# X7A15T-Fabric.net
KiCad netlist of a schematic drawn in Altium Designer
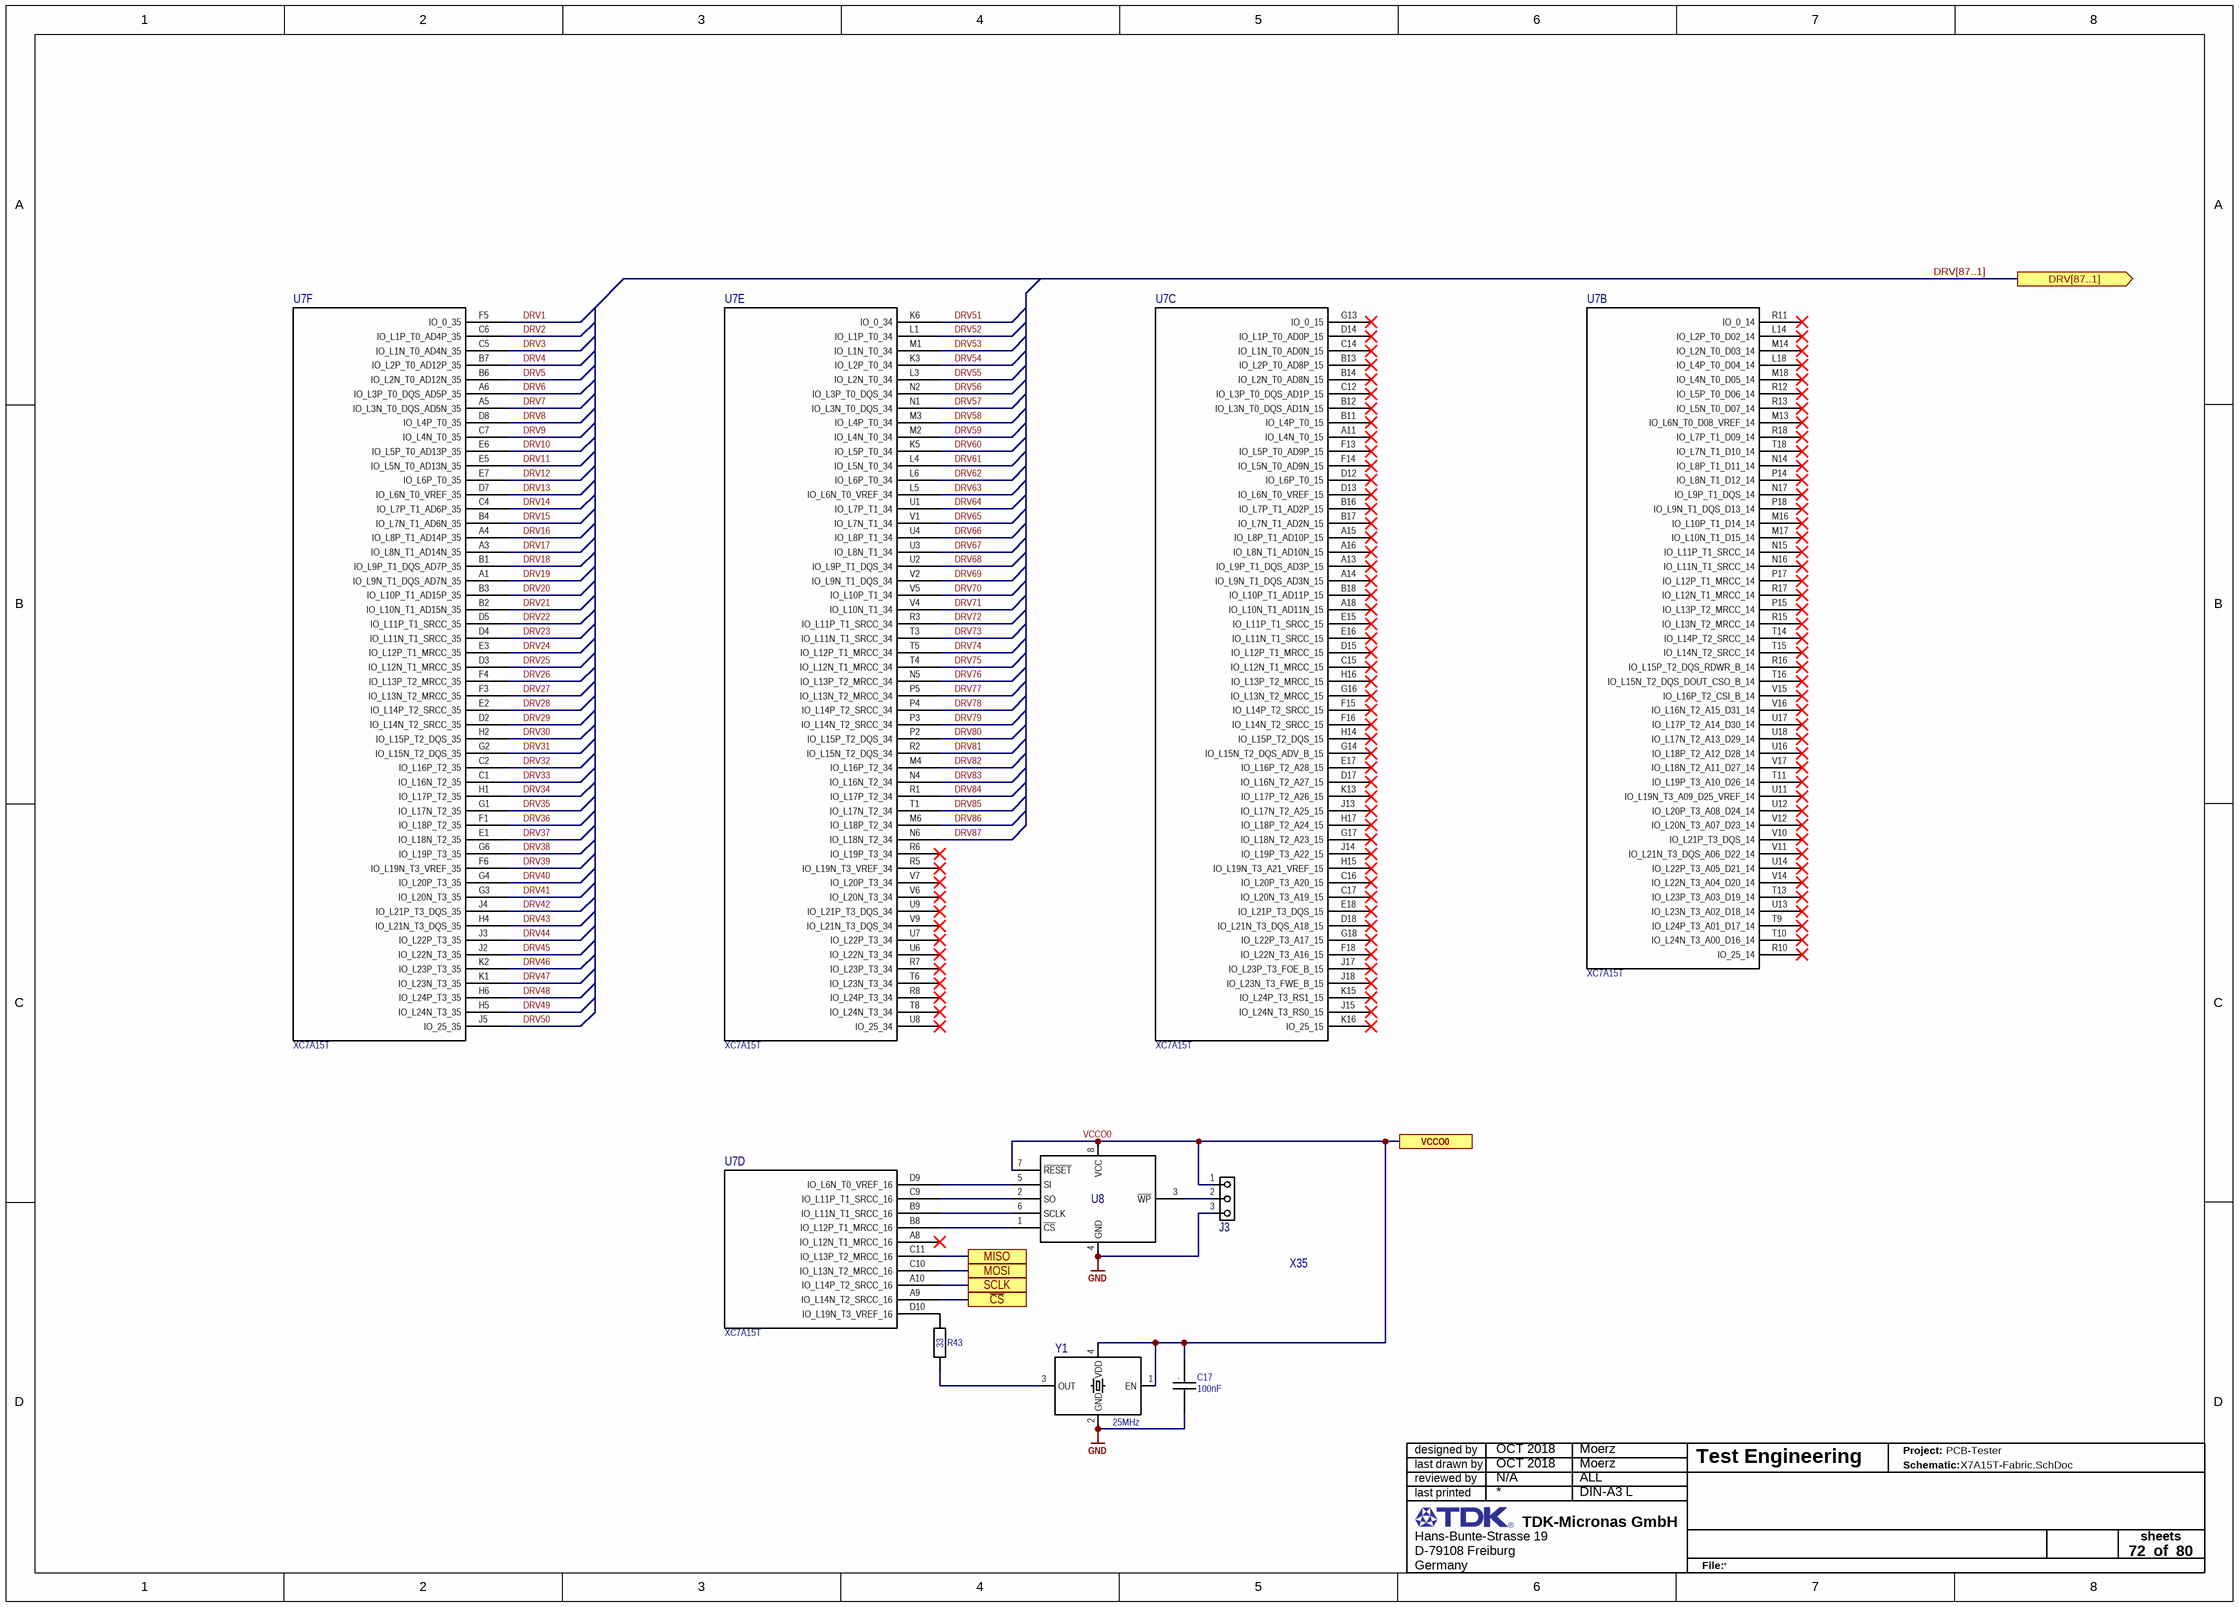
[diagram p0: X7A15T-Fabric.SchDoc]

(export (version "E")
  (design (tool "Eeschema 10.0.6"))
  (components
    (comp (ref "C17")
      (value "100nF")
      (footprint "C0402 Reflow")
      (description "CAP CER 0.1UF 16V X7R 0402")
      (fields
        (field (name "TOLERANCE") "±5%")
        (field (name "02. DISTRIBUTOR PART NUMBER") "399-7761-6-ND")
        (field (name "13. CREATED DATE/NAME") "AUG2018/Hören")
      )
      (libsource (lib "chickenfood") (part "C"))
    )
    (comp (ref "J3")
      (value "J")
      (footprint "Header 100mil 3x1")
      (description "CONN HEADER VERT 3POS 2.54MM")
      (fields
        (field (name "02. DISTRIBUTOR PART NUMBER") "HMTSW-103-07-G-S-240")
        (field (name "13. CREATED DATE/NAME") "AUG2018/Hören")
      )
      (libsource (lib "chickenfood") (part "Header 3Pins 100mil"))
    )
    (comp (ref "R43")
      (value "33")
      (footprint "R0402 Reflow")
      (description "RES SMD 33 OHM 1% 1/16W 0402")
      (fields
        (field (name "TOLERANCE") "±1%")
        (field (name "02. DISTRIBUTOR PART NUMBER") "311-33.0LRDKR-ND")
        (field (name "13. CREATED DATE/NAME") "AUG2018/Hören")
      )
      (libsource (lib "chickenfood") (part "R"))
    )
    (comp (ref "U7")
      (value "U")
      (footprint "XC7A15T-1CSG324C")
      (description "XC7A15T-1CSG324C")
      (fields (field (name "MFR") "XILINX") (field (name "NICNAME") "XC7A15T"))
      (libsource (lib "tom") (part "XC7A15T-CS324"))
    )
    (comp (ref "U8")
      (value "U")
      (footprint "SOIC8 (R-8)")
      (description "IC FLASH 32M SPI 80MHZ 8SOP")
      (fields (field (name "13. CREATED DATE/NAME") "AUG 2018 / Hören"))
      (libsource (lib "tom") (part "MX25R3235FM1IH0"))
    )
    (comp (ref "X35")
      (value "X")
      (description "CONN JUMPER SHORTING .100\" GOLD")
      (fields
        (field (name "02. DISTRIBUTOR PART NUMBER") "S9337-ND")
        (field (name "07. MANUFACTURER  PART NUMBER") "QPC02SXGN-RC")
        (field (name "13. CREATED DATE/NAME") "AUG2018/Hören")
      )
      (libsource (lib "chickenfood") (part "Jumper"))
    )
    (comp (ref "Y1")
      (value "Y")
      (footprint "4SMD")
      (description "XTAL OSC XO 25.0000MHZ CMOS SMD")
      (fields
        (field (name "02. DISTRIBUTOR PART NUMBER") "535-9568-1-ND")
        (field (name "07. MANUFACTURER  PART NUMBER") "ASE-25.000MHZ-LC-T")
        (field (name "FREQUENCY") "25MHz")
        (field (name "13. CREATED DATE/NAME") "AUG 2018 / Hören")
      )
      (libsource (lib "tom") (part "ASE-25.000MHZ-LC-T"))
    )
  )
  (nets
    (net (code "1") (name "/CS") (class "Default")
      (node (ref "U7") (pin "A9") (pinfunction "IO_L14N_T2_SRCC_16_A9") (pintype "passive"))
    )
    (net (code "2") (name "/DRV1") (class "Default")
      (node (ref "U7") (pin "F5") (pinfunction "IO_0_35_F5") (pintype "passive"))
    )
    (net (code "3") (name "/DRV2") (class "Default")
      (node (ref "U7") (pin "C6") (pinfunction "IO_L1P_T0_AD4P_35_C6") (pintype "passive"))
    )
    (net (code "4") (name "/DRV3") (class "Default")
      (node (ref "U7") (pin "C5") (pinfunction "IO_L1N_T0_AD4N_35_C5") (pintype "passive"))
    )
    (net (code "5") (name "/DRV4") (class "Default")
      (node (ref "U7") (pin "B7") (pinfunction "IO_L2P_T0_AD12P_35_B7") (pintype "passive"))
    )
    (net (code "6") (name "/DRV5") (class "Default")
      (node (ref "U7") (pin "B6") (pinfunction "IO_L2N_T0_AD12N_35_B6") (pintype "passive"))
    )
    (net (code "7") (name "/DRV6") (class "Default")
      (node (ref "U7") (pin "A6") (pinfunction "IO_L3P_T0_DQS_AD5P_35_A6") (pintype "passive"))
    )
    (net (code "8") (name "/DRV7") (class "Default")
      (node (ref "U7") (pin "A5") (pinfunction "IO_L3N_T0_DQS_AD5N_35_A5") (pintype "passive"))
    )
    (net (code "9") (name "/DRV8") (class "Default")
      (node (ref "U7") (pin "D8") (pinfunction "IO_L4P_T0_35_D8") (pintype "passive"))
    )
    (net (code "10") (name "/DRV9") (class "Default")
      (node (ref "U7") (pin "C7") (pinfunction "IO_L4N_T0_35_C7") (pintype "passive"))
    )
    (net (code "11") (name "/DRV10") (class "Default")
      (node (ref "U7") (pin "E6") (pinfunction "IO_L5P_T0_AD13P_35_E6") (pintype "passive"))
    )
    (net (code "12") (name "/DRV11") (class "Default")
      (node (ref "U7") (pin "E5") (pinfunction "IO_L5N_T0_AD13N_35_E5") (pintype "passive"))
    )
    (net (code "13") (name "/DRV12") (class "Default")
      (node (ref "U7") (pin "E7") (pinfunction "IO_L6P_T0_35_E7") (pintype "passive"))
    )
    (net (code "14") (name "/DRV13") (class "Default")
      (node (ref "U7") (pin "D7") (pinfunction "IO_L6N_T0_VREF_35_D7") (pintype "passive"))
    )
    (net (code "15") (name "/DRV14") (class "Default")
      (node (ref "U7") (pin "C4") (pinfunction "IO_L7P_T1_AD6P_35_C4") (pintype "passive"))
    )
    (net (code "16") (name "/DRV15") (class "Default")
      (node (ref "U7") (pin "B4") (pinfunction "IO_L7N_T1_AD6N_35_B4") (pintype "passive"))
    )
    (net (code "17") (name "/DRV16") (class "Default")
      (node (ref "U7") (pin "A4") (pinfunction "IO_L8P_T1_AD14P_35_A4") (pintype "passive"))
    )
    (net (code "18") (name "/DRV17") (class "Default")
      (node (ref "U7") (pin "A3") (pinfunction "IO_L8N_T1_AD14N_35_A3") (pintype "passive"))
    )
    (net (code "19") (name "/DRV18") (class "Default")
      (node (ref "U7") (pin "B1") (pinfunction "IO_L9P_T1_DQS_AD7P_35_B1") (pintype "passive"))
    )
    (net (code "20") (name "/DRV19") (class "Default")
      (node (ref "U7") (pin "A1") (pinfunction "IO_L9N_T1_DQS_AD7N_35_A1") (pintype "passive"))
    )
    (net (code "21") (name "/DRV20") (class "Default")
      (node (ref "U7") (pin "B3") (pinfunction "IO_L10P_T1_AD15P_35_B3") (pintype "passive"))
    )
    (net (code "22") (name "/DRV21") (class "Default")
      (node (ref "U7") (pin "B2") (pinfunction "IO_L10N_T1_AD15N_35_B2") (pintype "passive"))
    )
    (net (code "23") (name "/DRV22") (class "Default")
      (node (ref "U7") (pin "D5") (pinfunction "IO_L11P_T1_SRCC_35_D5") (pintype "passive"))
    )
    (net (code "24") (name "/DRV23") (class "Default")
      (node (ref "U7") (pin "D4") (pinfunction "IO_L11N_T1_SRCC_35_D4") (pintype "passive"))
    )
    (net (code "25") (name "/DRV24") (class "Default")
      (node (ref "U7") (pin "E3") (pinfunction "IO_L12P_T1_MRCC_35_E3") (pintype "passive"))
    )
    (net (code "26") (name "/DRV25") (class "Default")
      (node (ref "U7") (pin "D3") (pinfunction "IO_L12N_T1_MRCC_35_D3") (pintype "passive"))
    )
    (net (code "27") (name "/DRV26") (class "Default")
      (node (ref "U7") (pin "F4") (pinfunction "IO_L13P_T2_MRCC_35_F4") (pintype "passive"))
    )
    (net (code "28") (name "/DRV27") (class "Default")
      (node (ref "U7") (pin "F3") (pinfunction "IO_L13N_T2_MRCC_35_F3") (pintype "passive"))
    )
    (net (code "29") (name "/DRV28") (class "Default")
      (node (ref "U7") (pin "E2") (pinfunction "IO_L14P_T2_SRCC_35_E2") (pintype "passive"))
    )
    (net (code "30") (name "/DRV29") (class "Default")
      (node (ref "U7") (pin "D2") (pinfunction "IO_L14N_T2_SRCC_35_D2") (pintype "passive"))
    )
    (net (code "31") (name "/DRV30") (class "Default")
      (node (ref "U7") (pin "H2") (pinfunction "IO_L15P_T2_DQS_35_H2") (pintype "passive"))
    )
    (net (code "32") (name "/DRV31") (class "Default")
      (node (ref "U7") (pin "G2") (pinfunction "IO_L15N_T2_DQS_35_G2") (pintype "passive"))
    )
    (net (code "33") (name "/DRV32") (class "Default")
      (node (ref "U7") (pin "C2") (pinfunction "IO_L16P_T2_35_C2") (pintype "passive"))
    )
    (net (code "34") (name "/DRV33") (class "Default")
      (node (ref "U7") (pin "C1") (pinfunction "IO_L16N_T2_35_C1") (pintype "passive"))
    )
    (net (code "35") (name "/DRV34") (class "Default")
      (node (ref "U7") (pin "H1") (pinfunction "IO_L17P_T2_35_H1") (pintype "passive"))
    )
    (net (code "36") (name "/DRV35") (class "Default")
      (node (ref "U7") (pin "G1") (pinfunction "IO_L17N_T2_35_G1") (pintype "passive"))
    )
    (net (code "37") (name "/DRV36") (class "Default")
      (node (ref "U7") (pin "F1") (pinfunction "IO_L18P_T2_35_F1") (pintype "passive"))
    )
    (net (code "38") (name "/DRV37") (class "Default")
      (node (ref "U7") (pin "E1") (pinfunction "IO_L18N_T2_35_E1") (pintype "passive"))
    )
    (net (code "39") (name "/DRV38") (class "Default")
      (node (ref "U7") (pin "G6") (pinfunction "IO_L19P_T3_35_G6") (pintype "passive"))
    )
    (net (code "40") (name "/DRV39") (class "Default")
      (node (ref "U7") (pin "F6") (pinfunction "IO_L19N_T3_VREF_35_F6") (pintype "passive"))
    )
    (net (code "41") (name "/DRV40") (class "Default")
      (node (ref "U7") (pin "G4") (pinfunction "IO_L20P_T3_35_G4") (pintype "passive"))
    )
    (net (code "42") (name "/DRV41") (class "Default")
      (node (ref "U7") (pin "G3") (pinfunction "IO_L20N_T3_35_G3") (pintype "passive"))
    )
    (net (code "43") (name "/DRV42") (class "Default")
      (node (ref "U7") (pin "J4") (pinfunction "IO_L21P_T3_DQS_35_J4") (pintype "passive"))
    )
    (net (code "44") (name "/DRV43") (class "Default")
      (node (ref "U7") (pin "H4") (pinfunction "IO_L21N_T3_DQS_35_H4") (pintype "passive"))
    )
    (net (code "45") (name "/DRV44") (class "Default")
      (node (ref "U7") (pin "J3") (pinfunction "IO_L22P_T3_35_J3") (pintype "passive"))
    )
    (net (code "46") (name "/DRV45") (class "Default")
      (node (ref "U7") (pin "J2") (pinfunction "IO_L22N_T3_35_J2") (pintype "passive"))
    )
    (net (code "47") (name "/DRV46") (class "Default")
      (node (ref "U7") (pin "K2") (pinfunction "IO_L23P_T3_35_K2") (pintype "passive"))
    )
    (net (code "48") (name "/DRV47") (class "Default")
      (node (ref "U7") (pin "K1") (pinfunction "IO_L23N_T3_35_K1") (pintype "passive"))
    )
    (net (code "49") (name "/DRV48") (class "Default")
      (node (ref "U7") (pin "H6") (pinfunction "IO_L24P_T3_35_H6") (pintype "passive"))
    )
    (net (code "50") (name "/DRV49") (class "Default")
      (node (ref "U7") (pin "H5") (pinfunction "IO_L24N_T3_35_H5") (pintype "passive"))
    )
    (net (code "51") (name "/DRV50") (class "Default")
      (node (ref "U7") (pin "J5") (pinfunction "IO_25_35_J5") (pintype "passive"))
    )
    (net (code "52") (name "/DRV51") (class "Default")
      (node (ref "U7") (pin "K6") (pinfunction "IO_0_34_K6") (pintype "passive"))
    )
    (net (code "53") (name "/DRV52") (class "Default")
      (node (ref "U7") (pin "L1") (pinfunction "IO_L1P_T0_34_L1") (pintype "passive"))
    )
    (net (code "54") (name "/DRV53") (class "Default")
      (node (ref "U7") (pin "M1") (pinfunction "IO_L1N_T0_34_M1") (pintype "passive"))
    )
    (net (code "55") (name "/DRV54") (class "Default")
      (node (ref "U7") (pin "K3") (pinfunction "IO_L2P_T0_34_K3") (pintype "passive"))
    )
    (net (code "56") (name "/DRV55") (class "Default")
      (node (ref "U7") (pin "L3") (pinfunction "IO_L2N_T0_34_L3") (pintype "passive"))
    )
    (net (code "57") (name "/DRV56") (class "Default")
      (node (ref "U7") (pin "N2") (pinfunction "IO_L3P_T0_DQS_34_N2") (pintype "passive"))
    )
    (net (code "58") (name "/DRV57") (class "Default")
      (node (ref "U7") (pin "N1") (pinfunction "IO_L3N_T0_DQS_34_N1") (pintype "passive"))
    )
    (net (code "59") (name "/DRV58") (class "Default")
      (node (ref "U7") (pin "M3") (pinfunction "IO_L4P_T0_34_M3") (pintype "passive"))
    )
    (net (code "60") (name "/DRV59") (class "Default")
      (node (ref "U7") (pin "M2") (pinfunction "IO_L4N_T0_34_M2") (pintype "passive"))
    )
    (net (code "61") (name "/DRV60") (class "Default")
      (node (ref "U7") (pin "K5") (pinfunction "IO_L5P_T0_34_K5") (pintype "passive"))
    )
    (net (code "62") (name "/DRV61") (class "Default")
      (node (ref "U7") (pin "L4") (pinfunction "IO_L5N_T0_34_L4") (pintype "passive"))
    )
    (net (code "63") (name "/DRV62") (class "Default")
      (node (ref "U7") (pin "L6") (pinfunction "IO_L6P_T0_34_L6") (pintype "passive"))
    )
    (net (code "64") (name "/DRV63") (class "Default")
      (node (ref "U7") (pin "L5") (pinfunction "IO_L6N_T0_VREF_34_L5") (pintype "passive"))
    )
    (net (code "65") (name "/DRV64") (class "Default")
      (node (ref "U7") (pin "U1") (pinfunction "IO_L7P_T1_34_U1") (pintype "passive"))
    )
    (net (code "66") (name "/DRV65") (class "Default")
      (node (ref "U7") (pin "V1") (pinfunction "IO_L7N_T1_34_V1") (pintype "passive"))
    )
    (net (code "67") (name "/DRV66") (class "Default")
      (node (ref "U7") (pin "U4") (pinfunction "IO_L8P_T1_34_U4") (pintype "passive"))
    )
    (net (code "68") (name "/DRV67") (class "Default")
      (node (ref "U7") (pin "U3") (pinfunction "IO_L8N_T1_34_U3") (pintype "passive"))
    )
    (net (code "69") (name "/DRV68") (class "Default")
      (node (ref "U7") (pin "U2") (pinfunction "IO_L9P_T1_DQS_34_U2") (pintype "passive"))
    )
    (net (code "70") (name "/DRV69") (class "Default")
      (node (ref "U7") (pin "V2") (pinfunction "IO_L9N_T1_DQS_34_V2") (pintype "passive"))
    )
    (net (code "71") (name "/DRV70") (class "Default")
      (node (ref "U7") (pin "V5") (pinfunction "IO_L10P_T1_34_V5") (pintype "passive"))
    )
    (net (code "72") (name "/DRV71") (class "Default")
      (node (ref "U7") (pin "V4") (pinfunction "IO_L10N_T1_34_V4") (pintype "passive"))
    )
    (net (code "73") (name "/DRV72") (class "Default")
      (node (ref "U7") (pin "R3") (pinfunction "IO_L11P_T1_SRCC_34_R3") (pintype "passive"))
    )
    (net (code "74") (name "/DRV73") (class "Default")
      (node (ref "U7") (pin "T3") (pinfunction "IO_L11N_T1_SRCC_34_T3") (pintype "passive"))
    )
    (net (code "75") (name "/DRV74") (class "Default")
      (node (ref "U7") (pin "T5") (pinfunction "IO_L12P_T1_MRCC_34_T5") (pintype "passive"))
    )
    (net (code "76") (name "/DRV75") (class "Default")
      (node (ref "U7") (pin "T4") (pinfunction "IO_L12N_T1_MRCC_34_T4") (pintype "passive"))
    )
    (net (code "77") (name "/DRV76") (class "Default")
      (node (ref "U7") (pin "N5") (pinfunction "IO_L13P_T2_MRCC_34_N5") (pintype "passive"))
    )
    (net (code "78") (name "/DRV77") (class "Default")
      (node (ref "U7") (pin "P5") (pinfunction "IO_L13N_T2_MRCC_34_P5") (pintype "passive"))
    )
    (net (code "79") (name "/DRV78") (class "Default")
      (node (ref "U7") (pin "P4") (pinfunction "IO_L14P_T2_SRCC_34_P4") (pintype "passive"))
    )
    (net (code "80") (name "/DRV79") (class "Default")
      (node (ref "U7") (pin "P3") (pinfunction "IO_L14N_T2_SRCC_34_P3") (pintype "passive"))
    )
    (net (code "81") (name "/DRV80") (class "Default")
      (node (ref "U7") (pin "P2") (pinfunction "IO_L15P_T2_DQS_34_P2") (pintype "passive"))
    )
    (net (code "82") (name "/DRV81") (class "Default")
      (node (ref "U7") (pin "R2") (pinfunction "IO_L15N_T2_DQS_34_R2") (pintype "passive"))
    )
    (net (code "83") (name "/DRV82") (class "Default")
      (node (ref "U7") (pin "M4") (pinfunction "IO_L16P_T2_34_M4") (pintype "passive"))
    )
    (net (code "84") (name "/DRV83") (class "Default")
      (node (ref "U7") (pin "N4") (pinfunction "IO_L16N_T2_34_N4") (pintype "passive"))
    )
    (net (code "85") (name "/DRV84") (class "Default")
      (node (ref "U7") (pin "R1") (pinfunction "IO_L17P_T2_34_R1") (pintype "passive"))
    )
    (net (code "86") (name "/DRV85") (class "Default")
      (node (ref "U7") (pin "T1") (pinfunction "IO_L17N_T2_34_T1") (pintype "passive"))
    )
    (net (code "87") (name "/DRV86") (class "Default")
      (node (ref "U7") (pin "M6") (pinfunction "IO_L18P_T2_34_M6") (pintype "passive"))
    )
    (net (code "88") (name "/DRV87") (class "Default")
      (node (ref "U7") (pin "N6") (pinfunction "IO_L18N_T2_34_N6") (pintype "passive"))
    )
    (net (code "90") (name "/MISO") (class "Default")
      (node (ref "U7") (pin "C11") (pinfunction "IO_L13P_T2_MRCC_16_C11") (pintype "passive"))
    )
    (net (code "91") (name "/MOSI") (class "Default")
      (node (ref "U7") (pin "C10") (pinfunction "IO_L13N_T2_MRCC_16_C10") (pintype "passive"))
    )
    (net (code "92") (name "/SCLK") (class "Default")
      (node (ref "U7") (pin "A10") (pinfunction "IO_L14P_T2_SRCC_16_A10") (pintype "passive"))
    )
    (net (code "93") (name "/VCCO0") (class "Default")
      (node (ref "C17") (pin "1") (pinfunction "1_1") (pintype "passive"))
      (node (ref "J3") (pin "1") (pinfunction "1_1") (pintype "passive"))
      (node (ref "U8") (pin "7") (pinfunction "RESET_7") (pintype "passive"))
      (node (ref "U8") (pin "8") (pinfunction "VCC_8") (pintype "passive"))
      (node (ref "Y1") (pin "1") (pinfunction "EN_1") (pintype "passive"))
      (node (ref "Y1") (pin "4") (pinfunction "VDD_4") (pintype "passive"))
    )
    (net (code "94") (name "GND") (class "Default")
      (node (ref "C17") (pin "2") (pinfunction "2_2") (pintype "passive"))
      (node (ref "J3") (pin "3") (pinfunction "3_3") (pintype "passive"))
      (node (ref "U8") (pin "4") (pinfunction "GND_4") (pintype "passive"))
      (node (ref "Y1") (pin "2") (pinfunction "GND_2") (pintype "passive"))
    )
    (net (code "95") (name "Net-(U7D-IO_L6N_T0_VREF_16)") (class "Default")
      (node (ref "U7") (pin "D9") (pinfunction "IO_L6N_T0_VREF_16_D9") (pintype "passive"))
      (node (ref "U8") (pin "5") (pinfunction "SI_5") (pintype "passive"))
    )
    (net (code "96") (name "Net-(U7D-IO_L11N_T1_SRCC_16)") (class "Default")
      (node (ref "U7") (pin "B9") (pinfunction "IO_L11N_T1_SRCC_16_B9") (pintype "passive"))
      (node (ref "U8") (pin "6") (pinfunction "SCLK_6") (pintype "passive"))
    )
    (net (code "97") (name "Net-(U7D-IO_L11P_T1_SRCC_16)") (class "Default")
      (node (ref "U7") (pin "C9") (pinfunction "IO_L11P_T1_SRCC_16_C9") (pintype "passive"))
      (node (ref "U8") (pin "2") (pinfunction "SO_2") (pintype "passive"))
    )
    (net (code "98") (name "Net-(U7D-IO_L12P_T1_MRCC_16)") (class "Default")
      (node (ref "U7") (pin "B8") (pinfunction "IO_L12P_T1_MRCC_16_B8") (pintype "passive"))
      (node (ref "U8") (pin "1") (pinfunction "CS_1") (pintype "passive"))
    )
    (net (code "99") (name "Net-(U7D-IO_L19N_T3_VREF_16)") (class "Default")
      (node (ref "R43") (pin "2") (pinfunction "2_2") (pintype "passive"))
      (node (ref "U7") (pin "D10") (pinfunction "IO_L19N_T3_VREF_16_D10") (pintype "passive"))
    )
    (net (code "100") (name "Net-(U8-WP)") (class "Default")
      (node (ref "J3") (pin "2") (pinfunction "2_2") (pintype "passive"))
      (node (ref "U8") (pin "3") (pinfunction "WP_3") (pintype "passive"))
    )
    (net (code "101") (name "Net-(Y1-OUT)") (class "Default")
      (node (ref "R43") (pin "1") (pinfunction "1_1") (pintype "passive"))
      (node (ref "Y1") (pin "3") (pinfunction "OUT_3") (pintype "passive"))
    )
    (net (code "102") (name "unconnected-(U7B-IO_0_14-PadR11)") (class "Default")
      (node (ref "U7") (pin "R11") (pinfunction "IO_0_14_R11") (pintype "passive+no_connect"))
    )
    (net (code "103") (name "unconnected-(U7B-IO_25_14-PadR10)") (class "Default")
      (node (ref "U7") (pin "R10") (pinfunction "IO_25_14_R10") (pintype "passive+no_connect"))
    )
    (net (code "104") (name "unconnected-(U7B-IO_L2N_T0_D03_14-PadM14)") (class "Default")
      (node (ref "U7") (pin "M14") (pinfunction "IO_L2N_T0_D03_14_M14") (pintype "passive+no_connect"))
    )
    (net (code "105") (name "unconnected-(U7B-IO_L2P_T0_D02_14-PadL14)") (class "Default")
      (node (ref "U7") (pin "L14") (pinfunction "IO_L2P_T0_D02_14_L14") (pintype "passive+no_connect"))
    )
    (net (code "106") (name "unconnected-(U7B-IO_L4N_T0_D05_14-PadM18)") (class "Default")
      (node (ref "U7") (pin "M18") (pinfunction "IO_L4N_T0_D05_14_M18") (pintype "passive+no_connect"))
    )
    (net (code "107") (name "unconnected-(U7B-IO_L4P_T0_D04_14-PadL18)") (class "Default")
      (node (ref "U7") (pin "L18") (pinfunction "IO_L4P_T0_D04_14_L18") (pintype "passive+no_connect"))
    )
    (net (code "108") (name "unconnected-(U7B-IO_L5N_T0_D07_14-PadR13)") (class "Default")
      (node (ref "U7") (pin "R13") (pinfunction "IO_L5N_T0_D07_14_R13") (pintype "passive+no_connect"))
    )
    (net (code "109") (name "unconnected-(U7B-IO_L5P_T0_D06_14-PadR12)") (class "Default")
      (node (ref "U7") (pin "R12") (pinfunction "IO_L5P_T0_D06_14_R12") (pintype "passive+no_connect"))
    )
    (net (code "110") (name "unconnected-(U7B-IO_L6N_T0_D08_VREF_14-PadM13)") (class "Default")
      (node (ref "U7") (pin "M13") (pinfunction "IO_L6N_T0_D08_VREF_14_M13") (pintype "passive+no_connect"))
    )
    (net (code "111") (name "unconnected-(U7B-IO_L7N_T1_D10_14-PadT18)") (class "Default")
      (node (ref "U7") (pin "T18") (pinfunction "IO_L7N_T1_D10_14_T18") (pintype "passive+no_connect"))
    )
    (net (code "112") (name "unconnected-(U7B-IO_L7P_T1_D09_14-PadR18)") (class "Default")
      (node (ref "U7") (pin "R18") (pinfunction "IO_L7P_T1_D09_14_R18") (pintype "passive+no_connect"))
    )
    (net (code "113") (name "unconnected-(U7B-IO_L8N_T1_D12_14-PadP14)") (class "Default")
      (node (ref "U7") (pin "P14") (pinfunction "IO_L8N_T1_D12_14_P14") (pintype "passive+no_connect"))
    )
    (net (code "114") (name "unconnected-(U7B-IO_L8P_T1_D11_14-PadN14)") (class "Default")
      (node (ref "U7") (pin "N14") (pinfunction "IO_L8P_T1_D11_14_N14") (pintype "passive+no_connect"))
    )
    (net (code "115") (name "unconnected-(U7B-IO_L9N_T1_DQS_D13_14-PadP18)") (class "Default")
      (node (ref "U7") (pin "P18") (pinfunction "IO_L9N_T1_DQS_D13_14_P18") (pintype "passive+no_connect"))
    )
    (net (code "116") (name "unconnected-(U7B-IO_L9P_T1_DQS_14-PadN17)") (class "Default")
      (node (ref "U7") (pin "N17") (pinfunction "IO_L9P_T1_DQS_14_N17") (pintype "passive+no_connect"))
    )
    (net (code "117") (name "unconnected-(U7B-IO_L10N_T1_D15_14-PadM17)") (class "Default")
      (node (ref "U7") (pin "M17") (pinfunction "IO_L10N_T1_D15_14_M17") (pintype "passive+no_connect"))
    )
    (net (code "118") (name "unconnected-(U7B-IO_L10P_T1_D14_14-PadM16)") (class "Default")
      (node (ref "U7") (pin "M16") (pinfunction "IO_L10P_T1_D14_14_M16") (pintype "passive+no_connect"))
    )
    (net (code "119") (name "unconnected-(U7B-IO_L11N_T1_SRCC_14-PadN16)") (class "Default")
      (node (ref "U7") (pin "N16") (pinfunction "IO_L11N_T1_SRCC_14_N16") (pintype "passive+no_connect"))
    )
    (net (code "120") (name "unconnected-(U7B-IO_L11P_T1_SRCC_14-PadN15)") (class "Default")
      (node (ref "U7") (pin "N15") (pinfunction "IO_L11P_T1_SRCC_14_N15") (pintype "passive+no_connect"))
    )
    (net (code "121") (name "unconnected-(U7B-IO_L12N_T1_MRCC_14-PadR17)") (class "Default")
      (node (ref "U7") (pin "R17") (pinfunction "IO_L12N_T1_MRCC_14_R17") (pintype "passive+no_connect"))
    )
    (net (code "122") (name "unconnected-(U7B-IO_L12P_T1_MRCC_14-PadP17)") (class "Default")
      (node (ref "U7") (pin "P17") (pinfunction "IO_L12P_T1_MRCC_14_P17") (pintype "passive+no_connect"))
    )
    (net (code "123") (name "unconnected-(U7B-IO_L13N_T2_MRCC_14-PadR15)") (class "Default")
      (node (ref "U7") (pin "R15") (pinfunction "IO_L13N_T2_MRCC_14_R15") (pintype "passive+no_connect"))
    )
    (net (code "124") (name "unconnected-(U7B-IO_L13P_T2_MRCC_14-PadP15)") (class "Default")
      (node (ref "U7") (pin "P15") (pinfunction "IO_L13P_T2_MRCC_14_P15") (pintype "passive+no_connect"))
    )
    (net (code "125") (name "unconnected-(U7B-IO_L14N_T2_SRCC_14-PadT15)") (class "Default")
      (node (ref "U7") (pin "T15") (pinfunction "IO_L14N_T2_SRCC_14_T15") (pintype "passive+no_connect"))
    )
    (net (code "126") (name "unconnected-(U7B-IO_L14P_T2_SRCC_14-PadT14)") (class "Default")
      (node (ref "U7") (pin "T14") (pinfunction "IO_L14P_T2_SRCC_14_T14") (pintype "passive+no_connect"))
    )
    (net (code "127") (name "unconnected-(U7B-IO_L15N_T2_DQS_DOUT_CSO_B_14-PadT16)") (class "Default")
      (node (ref "U7") (pin "T16") (pinfunction "IO_L15N_T2_DQS_DOUT_CSO_B_14_T16") (pintype "passive+no_connect"))
    )
    (net (code "128") (name "unconnected-(U7B-IO_L15P_T2_DQS_RDWR_B_14-PadR16)") (class "Default")
      (node (ref "U7") (pin "R16") (pinfunction "IO_L15P_T2_DQS_RDWR_B_14_R16") (pintype "passive+no_connect"))
    )
    (net (code "129") (name "unconnected-(U7B-IO_L16N_T2_A15_D31_14-PadV16)") (class "Default")
      (node (ref "U7") (pin "V16") (pinfunction "IO_L16N_T2_A15_D31_14_V16") (pintype "passive+no_connect"))
    )
    (net (code "130") (name "unconnected-(U7B-IO_L16P_T2_CSI_B_14-PadV15)") (class "Default")
      (node (ref "U7") (pin "V15") (pinfunction "IO_L16P_T2_CSI_B_14_V15") (pintype "passive+no_connect"))
    )
    (net (code "131") (name "unconnected-(U7B-IO_L17N_T2_A13_D29_14-PadU18)") (class "Default")
      (node (ref "U7") (pin "U18") (pinfunction "IO_L17N_T2_A13_D29_14_U18") (pintype "passive+no_connect"))
    )
    (net (code "132") (name "unconnected-(U7B-IO_L17P_T2_A14_D30_14-PadU17)") (class "Default")
      (node (ref "U7") (pin "U17") (pinfunction "IO_L17P_T2_A14_D30_14_U17") (pintype "passive+no_connect"))
    )
    (net (code "133") (name "unconnected-(U7B-IO_L18N_T2_A11_D27_14-PadV17)") (class "Default")
      (node (ref "U7") (pin "V17") (pinfunction "IO_L18N_T2_A11_D27_14_V17") (pintype "passive+no_connect"))
    )
    (net (code "134") (name "unconnected-(U7B-IO_L18P_T2_A12_D28_14-PadU16)") (class "Default")
      (node (ref "U7") (pin "U16") (pinfunction "IO_L18P_T2_A12_D28_14_U16") (pintype "passive+no_connect"))
    )
    (net (code "135") (name "unconnected-(U7B-IO_L19N_T3_A09_D25_VREF_14-PadU11)") (class "Default")
      (node (ref "U7") (pin "U11") (pinfunction "IO_L19N_T3_A09_D25_VREF_14_U11") (pintype "passive+no_connect"))
    )
    (net (code "136") (name "unconnected-(U7B-IO_L19P_T3_A10_D26_14-PadT11)") (class "Default")
      (node (ref "U7") (pin "T11") (pinfunction "IO_L19P_T3_A10_D26_14_T11") (pintype "passive+no_connect"))
    )
    (net (code "137") (name "unconnected-(U7B-IO_L20N_T3_A07_D23_14-PadV12)") (class "Default")
      (node (ref "U7") (pin "V12") (pinfunction "IO_L20N_T3_A07_D23_14_V12") (pintype "passive+no_connect"))
    )
    (net (code "138") (name "unconnected-(U7B-IO_L20P_T3_A08_D24_14-PadU12)") (class "Default")
      (node (ref "U7") (pin "U12") (pinfunction "IO_L20P_T3_A08_D24_14_U12") (pintype "passive+no_connect"))
    )
    (net (code "139") (name "unconnected-(U7B-IO_L21N_T3_DQS_A06_D22_14-PadV11)") (class "Default")
      (node (ref "U7") (pin "V11") (pinfunction "IO_L21N_T3_DQS_A06_D22_14_V11") (pintype "passive+no_connect"))
    )
    (net (code "140") (name "unconnected-(U7B-IO_L21P_T3_DQS_14-PadV10)") (class "Default")
      (node (ref "U7") (pin "V10") (pinfunction "IO_L21P_T3_DQS_14_V10") (pintype "passive+no_connect"))
    )
    (net (code "141") (name "unconnected-(U7B-IO_L22N_T3_A04_D20_14-PadV14)") (class "Default")
      (node (ref "U7") (pin "V14") (pinfunction "IO_L22N_T3_A04_D20_14_V14") (pintype "passive+no_connect"))
    )
    (net (code "142") (name "unconnected-(U7B-IO_L22P_T3_A05_D21_14-PadU14)") (class "Default")
      (node (ref "U7") (pin "U14") (pinfunction "IO_L22P_T3_A05_D21_14_U14") (pintype "passive+no_connect"))
    )
    (net (code "143") (name "unconnected-(U7B-IO_L23N_T3_A02_D18_14-PadU13)") (class "Default")
      (node (ref "U7") (pin "U13") (pinfunction "IO_L23N_T3_A02_D18_14_U13") (pintype "passive+no_connect"))
    )
    (net (code "144") (name "unconnected-(U7B-IO_L23P_T3_A03_D19_14-PadT13)") (class "Default")
      (node (ref "U7") (pin "T13") (pinfunction "IO_L23P_T3_A03_D19_14_T13") (pintype "passive+no_connect"))
    )
    (net (code "145") (name "unconnected-(U7B-IO_L24N_T3_A00_D16_14-PadT10)") (class "Default")
      (node (ref "U7") (pin "T10") (pinfunction "IO_L24N_T3_A00_D16_14_T10") (pintype "passive+no_connect"))
    )
    (net (code "146") (name "unconnected-(U7B-IO_L24P_T3_A01_D17_14-PadT9)") (class "Default")
      (node (ref "U7") (pin "T9") (pinfunction "IO_L24P_T3_A01_D17_14_T9") (pintype "passive+no_connect"))
    )
    (net (code "147") (name "unconnected-(U7C-IO_0_15-PadG13)") (class "Default")
      (node (ref "U7") (pin "G13") (pinfunction "IO_0_15_G13") (pintype "passive+no_connect"))
    )
    (net (code "148") (name "unconnected-(U7C-IO_25_15-PadK16)") (class "Default")
      (node (ref "U7") (pin "K16") (pinfunction "IO_25_15_K16") (pintype "passive+no_connect"))
    )
    (net (code "149") (name "unconnected-(U7C-IO_L1N_T0_AD0N_15-PadC14)") (class "Default")
      (node (ref "U7") (pin "C14") (pinfunction "IO_L1N_T0_AD0N_15_C14") (pintype "passive+no_connect"))
    )
    (net (code "150") (name "unconnected-(U7C-IO_L1P_T0_AD0P_15-PadD14)") (class "Default")
      (node (ref "U7") (pin "D14") (pinfunction "IO_L1P_T0_AD0P_15_D14") (pintype "passive+no_connect"))
    )
    (net (code "151") (name "unconnected-(U7C-IO_L2N_T0_AD8N_15-PadB14)") (class "Default")
      (node (ref "U7") (pin "B14") (pinfunction "IO_L2N_T0_AD8N_15_B14") (pintype "passive+no_connect"))
    )
    (net (code "152") (name "unconnected-(U7C-IO_L2P_T0_AD8P_15-PadB13)") (class "Default")
      (node (ref "U7") (pin "B13") (pinfunction "IO_L2P_T0_AD8P_15_B13") (pintype "passive+no_connect"))
    )
    (net (code "153") (name "unconnected-(U7C-IO_L3N_T0_DQS_AD1N_15-PadB12)") (class "Default")
      (node (ref "U7") (pin "B12") (pinfunction "IO_L3N_T0_DQS_AD1N_15_B12") (pintype "passive+no_connect"))
    )
    (net (code "154") (name "unconnected-(U7C-IO_L3P_T0_DQS_AD1P_15-PadC12)") (class "Default")
      (node (ref "U7") (pin "C12") (pinfunction "IO_L3P_T0_DQS_AD1P_15_C12") (pintype "passive+no_connect"))
    )
    (net (code "155") (name "unconnected-(U7C-IO_L4N_T0_15-PadA11)") (class "Default")
      (node (ref "U7") (pin "A11") (pinfunction "IO_L4N_T0_15_A11") (pintype "passive+no_connect"))
    )
    (net (code "156") (name "unconnected-(U7C-IO_L4P_T0_15-PadB11)") (class "Default")
      (node (ref "U7") (pin "B11") (pinfunction "IO_L4P_T0_15_B11") (pintype "passive+no_connect"))
    )
    (net (code "157") (name "unconnected-(U7C-IO_L5N_T0_AD9N_15-PadF14)") (class "Default")
      (node (ref "U7") (pin "F14") (pinfunction "IO_L5N_T0_AD9N_15_F14") (pintype "passive+no_connect"))
    )
    (net (code "158") (name "unconnected-(U7C-IO_L5P_T0_AD9P_15-PadF13)") (class "Default")
      (node (ref "U7") (pin "F13") (pinfunction "IO_L5P_T0_AD9P_15_F13") (pintype "passive+no_connect"))
    )
    (net (code "159") (name "unconnected-(U7C-IO_L6N_T0_VREF_15-PadD13)") (class "Default")
      (node (ref "U7") (pin "D13") (pinfunction "IO_L6N_T0_VREF_15_D13") (pintype "passive+no_connect"))
    )
    (net (code "160") (name "unconnected-(U7C-IO_L6P_T0_15-PadD12)") (class "Default")
      (node (ref "U7") (pin "D12") (pinfunction "IO_L6P_T0_15_D12") (pintype "passive+no_connect"))
    )
    (net (code "161") (name "unconnected-(U7C-IO_L7N_T1_AD2N_15-PadB17)") (class "Default")
      (node (ref "U7") (pin "B17") (pinfunction "IO_L7N_T1_AD2N_15_B17") (pintype "passive+no_connect"))
    )
    (net (code "162") (name "unconnected-(U7C-IO_L7P_T1_AD2P_15-PadB16)") (class "Default")
      (node (ref "U7") (pin "B16") (pinfunction "IO_L7P_T1_AD2P_15_B16") (pintype "passive+no_connect"))
    )
    (net (code "163") (name "unconnected-(U7C-IO_L8N_T1_AD10N_15-PadA16)") (class "Default")
      (node (ref "U7") (pin "A16") (pinfunction "IO_L8N_T1_AD10N_15_A16") (pintype "passive+no_connect"))
    )
    (net (code "164") (name "unconnected-(U7C-IO_L8P_T1_AD10P_15-PadA15)") (class "Default")
      (node (ref "U7") (pin "A15") (pinfunction "IO_L8P_T1_AD10P_15_A15") (pintype "passive+no_connect"))
    )
    (net (code "165") (name "unconnected-(U7C-IO_L9N_T1_DQS_AD3N_15-PadA14)") (class "Default")
      (node (ref "U7") (pin "A14") (pinfunction "IO_L9N_T1_DQS_AD3N_15_A14") (pintype "passive+no_connect"))
    )
    (net (code "166") (name "unconnected-(U7C-IO_L9P_T1_DQS_AD3P_15-PadA13)") (class "Default")
      (node (ref "U7") (pin "A13") (pinfunction "IO_L9P_T1_DQS_AD3P_15_A13") (pintype "passive+no_connect"))
    )
    (net (code "167") (name "unconnected-(U7C-IO_L10N_T1_AD11N_15-PadA18)") (class "Default")
      (node (ref "U7") (pin "A18") (pinfunction "IO_L10N_T1_AD11N_15_A18") (pintype "passive+no_connect"))
    )
    (net (code "168") (name "unconnected-(U7C-IO_L10P_T1_AD11P_15-PadB18)") (class "Default")
      (node (ref "U7") (pin "B18") (pinfunction "IO_L10P_T1_AD11P_15_B18") (pintype "passive+no_connect"))
    )
    (net (code "169") (name "unconnected-(U7C-IO_L11N_T1_SRCC_15-PadE16)") (class "Default")
      (node (ref "U7") (pin "E16") (pinfunction "IO_L11N_T1_SRCC_15_E16") (pintype "passive+no_connect"))
    )
    (net (code "170") (name "unconnected-(U7C-IO_L11P_T1_SRCC_15-PadE15)") (class "Default")
      (node (ref "U7") (pin "E15") (pinfunction "IO_L11P_T1_SRCC_15_E15") (pintype "passive+no_connect"))
    )
    (net (code "171") (name "unconnected-(U7C-IO_L12N_T1_MRCC_15-PadC15)") (class "Default")
      (node (ref "U7") (pin "C15") (pinfunction "IO_L12N_T1_MRCC_15_C15") (pintype "passive+no_connect"))
    )
    (net (code "172") (name "unconnected-(U7C-IO_L12P_T1_MRCC_15-PadD15)") (class "Default")
      (node (ref "U7") (pin "D15") (pinfunction "IO_L12P_T1_MRCC_15_D15") (pintype "passive+no_connect"))
    )
    (net (code "173") (name "unconnected-(U7C-IO_L13N_T2_MRCC_15-PadG16)") (class "Default")
      (node (ref "U7") (pin "G16") (pinfunction "IO_L13N_T2_MRCC_15_G16") (pintype "passive+no_connect"))
    )
    (net (code "174") (name "unconnected-(U7C-IO_L13P_T2_MRCC_15-PadH16)") (class "Default")
      (node (ref "U7") (pin "H16") (pinfunction "IO_L13P_T2_MRCC_15_H16") (pintype "passive+no_connect"))
    )
    (net (code "175") (name "unconnected-(U7C-IO_L14N_T2_SRCC_15-PadF16)") (class "Default")
      (node (ref "U7") (pin "F16") (pinfunction "IO_L14N_T2_SRCC_15_F16") (pintype "passive+no_connect"))
    )
    (net (code "176") (name "unconnected-(U7C-IO_L14P_T2_SRCC_15-PadF15)") (class "Default")
      (node (ref "U7") (pin "F15") (pinfunction "IO_L14P_T2_SRCC_15_F15") (pintype "passive+no_connect"))
    )
    (net (code "177") (name "unconnected-(U7C-IO_L15N_T2_DQS_ADV_B_15-PadG14)") (class "Default")
      (node (ref "U7") (pin "G14") (pinfunction "IO_L15N_T2_DQS_ADV_B_15_G14") (pintype "passive+no_connect"))
    )
    (net (code "178") (name "unconnected-(U7C-IO_L15P_T2_DQS_15-PadH14)") (class "Default")
      (node (ref "U7") (pin "H14") (pinfunction "IO_L15P_T2_DQS_15_H14") (pintype "passive+no_connect"))
    )
    (net (code "179") (name "unconnected-(U7C-IO_L16N_T2_A27_15-PadD17)") (class "Default")
      (node (ref "U7") (pin "D17") (pinfunction "IO_L16N_T2_A27_15_D17") (pintype "passive+no_connect"))
    )
    (net (code "180") (name "unconnected-(U7C-IO_L16P_T2_A28_15-PadE17)") (class "Default")
      (node (ref "U7") (pin "E17") (pinfunction "IO_L16P_T2_A28_15_E17") (pintype "passive+no_connect"))
    )
    (net (code "181") (name "unconnected-(U7C-IO_L17N_T2_A25_15-PadJ13)") (class "Default")
      (node (ref "U7") (pin "J13") (pinfunction "IO_L17N_T2_A25_15_J13") (pintype "passive+no_connect"))
    )
    (net (code "182") (name "unconnected-(U7C-IO_L17P_T2_A26_15-PadK13)") (class "Default")
      (node (ref "U7") (pin "K13") (pinfunction "IO_L17P_T2_A26_15_K13") (pintype "passive+no_connect"))
    )
    (net (code "183") (name "unconnected-(U7C-IO_L18N_T2_A23_15-PadG17)") (class "Default")
      (node (ref "U7") (pin "G17") (pinfunction "IO_L18N_T2_A23_15_G17") (pintype "passive+no_connect"))
    )
    (net (code "184") (name "unconnected-(U7C-IO_L18P_T2_A24_15-PadH17)") (class "Default")
      (node (ref "U7") (pin "H17") (pinfunction "IO_L18P_T2_A24_15_H17") (pintype "passive+no_connect"))
    )
    (net (code "185") (name "unconnected-(U7C-IO_L19N_T3_A21_VREF_15-PadH15)") (class "Default")
      (node (ref "U7") (pin "H15") (pinfunction "IO_L19N_T3_A21_VREF_15_H15") (pintype "passive+no_connect"))
    )
    (net (code "186") (name "unconnected-(U7C-IO_L19P_T3_A22_15-PadJ14)") (class "Default")
      (node (ref "U7") (pin "J14") (pinfunction "IO_L19P_T3_A22_15_J14") (pintype "passive+no_connect"))
    )
    (net (code "187") (name "unconnected-(U7C-IO_L20N_T3_A19_15-PadC17)") (class "Default")
      (node (ref "U7") (pin "C17") (pinfunction "IO_L20N_T3_A19_15_C17") (pintype "passive+no_connect"))
    )
    (net (code "188") (name "unconnected-(U7C-IO_L20P_T3_A20_15-PadC16)") (class "Default")
      (node (ref "U7") (pin "C16") (pinfunction "IO_L20P_T3_A20_15_C16") (pintype "passive+no_connect"))
    )
    (net (code "189") (name "unconnected-(U7C-IO_L21N_T3_DQS_A18_15-PadD18)") (class "Default")
      (node (ref "U7") (pin "D18") (pinfunction "IO_L21N_T3_DQS_A18_15_D18") (pintype "passive+no_connect"))
    )
    (net (code "190") (name "unconnected-(U7C-IO_L21P_T3_DQS_15-PadE18)") (class "Default")
      (node (ref "U7") (pin "E18") (pinfunction "IO_L21P_T3_DQS_15_E18") (pintype "passive+no_connect"))
    )
    (net (code "191") (name "unconnected-(U7C-IO_L22N_T3_A16_15-PadF18)") (class "Default")
      (node (ref "U7") (pin "F18") (pinfunction "IO_L22N_T3_A16_15_F18") (pintype "passive+no_connect"))
    )
    (net (code "192") (name "unconnected-(U7C-IO_L22P_T3_A17_15-PadG18)") (class "Default")
      (node (ref "U7") (pin "G18") (pinfunction "IO_L22P_T3_A17_15_G18") (pintype "passive+no_connect"))
    )
    (net (code "193") (name "unconnected-(U7C-IO_L23N_T3_FWE_B_15-PadJ18)") (class "Default")
      (node (ref "U7") (pin "J18") (pinfunction "IO_L23N_T3_FWE_B_15_J18") (pintype "passive+no_connect"))
    )
    (net (code "194") (name "unconnected-(U7C-IO_L23P_T3_FOE_B_15-PadJ17)") (class "Default")
      (node (ref "U7") (pin "J17") (pinfunction "IO_L23P_T3_FOE_B_15_J17") (pintype "passive+no_connect"))
    )
    (net (code "195") (name "unconnected-(U7C-IO_L24N_T3_RS0_15-PadJ15)") (class "Default")
      (node (ref "U7") (pin "J15") (pinfunction "IO_L24N_T3_RS0_15_J15") (pintype "passive+no_connect"))
    )
    (net (code "196") (name "unconnected-(U7C-IO_L24P_T3_RS1_15-PadK15)") (class "Default")
      (node (ref "U7") (pin "K15") (pinfunction "IO_L24P_T3_RS1_15_K15") (pintype "passive+no_connect"))
    )
    (net (code "197") (name "unconnected-(U7D-IO_L12N_T1_MRCC_16-PadA8)") (class "Default")
      (node (ref "U7") (pin "A8") (pinfunction "IO_L12N_T1_MRCC_16_A8") (pintype "passive+no_connect"))
    )
    (net (code "198") (name "unconnected-(U7E-IO_25_34-PadU8)") (class "Default")
      (node (ref "U7") (pin "U8") (pinfunction "IO_25_34_U8") (pintype "passive+no_connect"))
    )
    (net (code "199") (name "unconnected-(U7E-IO_L19N_T3_VREF_34-PadR5)") (class "Default")
      (node (ref "U7") (pin "R5") (pinfunction "IO_L19N_T3_VREF_34_R5") (pintype "passive+no_connect"))
    )
    (net (code "200") (name "unconnected-(U7E-IO_L19P_T3_34-PadR6)") (class "Default")
      (node (ref "U7") (pin "R6") (pinfunction "IO_L19P_T3_34_R6") (pintype "passive+no_connect"))
    )
    (net (code "201") (name "unconnected-(U7E-IO_L20N_T3_34-PadV6)") (class "Default")
      (node (ref "U7") (pin "V6") (pinfunction "IO_L20N_T3_34_V6") (pintype "passive+no_connect"))
    )
    (net (code "202") (name "unconnected-(U7E-IO_L20P_T3_34-PadV7)") (class "Default")
      (node (ref "U7") (pin "V7") (pinfunction "IO_L20P_T3_34_V7") (pintype "passive+no_connect"))
    )
    (net (code "203") (name "unconnected-(U7E-IO_L21N_T3_DQS_34-PadV9)") (class "Default")
      (node (ref "U7") (pin "V9") (pinfunction "IO_L21N_T3_DQS_34_V9") (pintype "passive+no_connect"))
    )
    (net (code "204") (name "unconnected-(U7E-IO_L21P_T3_DQS_34-PadU9)") (class "Default")
      (node (ref "U7") (pin "U9") (pinfunction "IO_L21P_T3_DQS_34_U9") (pintype "passive+no_connect"))
    )
    (net (code "205") (name "unconnected-(U7E-IO_L22N_T3_34-PadU6)") (class "Default")
      (node (ref "U7") (pin "U6") (pinfunction "IO_L22N_T3_34_U6") (pintype "passive+no_connect"))
    )
    (net (code "206") (name "unconnected-(U7E-IO_L22P_T3_34-PadU7)") (class "Default")
      (node (ref "U7") (pin "U7") (pinfunction "IO_L22P_T3_34_U7") (pintype "passive+no_connect"))
    )
    (net (code "207") (name "unconnected-(U7E-IO_L23N_T3_34-PadT6)") (class "Default")
      (node (ref "U7") (pin "T6") (pinfunction "IO_L23N_T3_34_T6") (pintype "passive+no_connect"))
    )
    (net (code "208") (name "unconnected-(U7E-IO_L23P_T3_34-PadR7)") (class "Default")
      (node (ref "U7") (pin "R7") (pinfunction "IO_L23P_T3_34_R7") (pintype "passive+no_connect"))
    )
    (net (code "209") (name "unconnected-(U7E-IO_L24N_T3_34-PadT8)") (class "Default")
      (node (ref "U7") (pin "T8") (pinfunction "IO_L24N_T3_34_T8") (pintype "passive+no_connect"))
    )
    (net (code "210") (name "unconnected-(U7E-IO_L24P_T3_34-PadR8)") (class "Default")
      (node (ref "U7") (pin "R8") (pinfunction "IO_L24P_T3_34_R8") (pintype "passive+no_connect"))
    )
  )
)
